# 16V_VBatt_External.net
KiCad netlist of a schematic drawn in Altium Designer
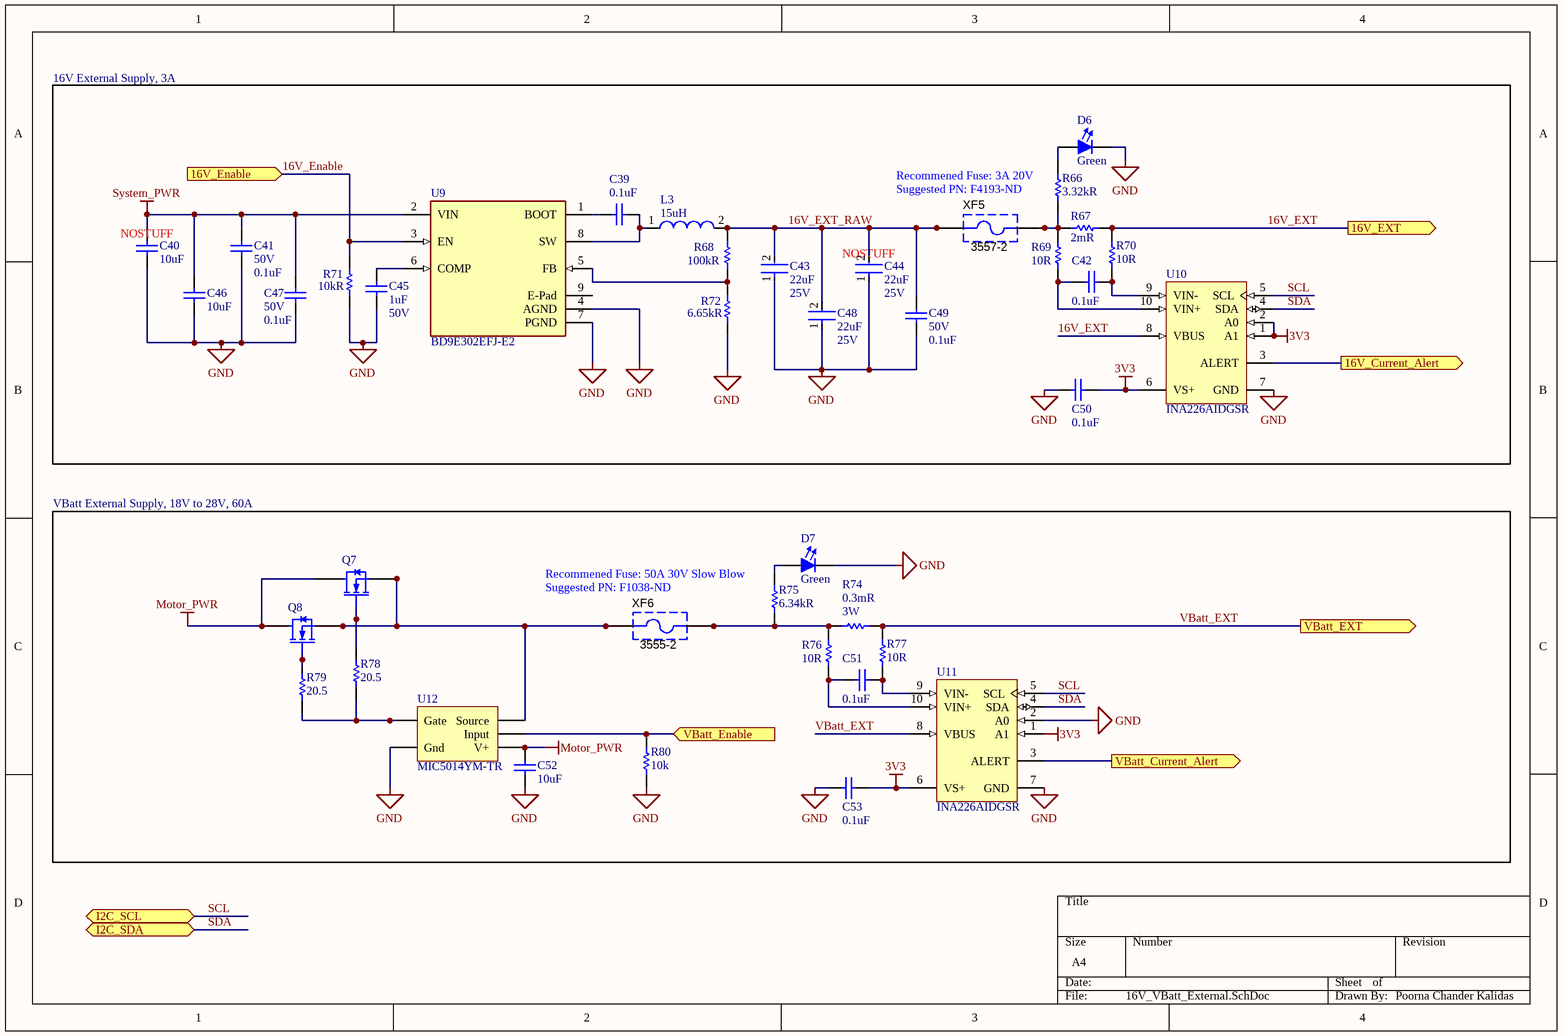
[diagram p0: 16V_VBatt_External.SchDoc]

(export (version "E")
  (design (tool "Eeschema 10.0.6"))
  (components
    (comp (ref "C39")
      (value "CL10B104JB8NNNC")
      (footprint "FP-CL10-0_1-IPC_A")
      (description "CAP CER 0.1UF 50V X7R 0603")
      (fields
        (field (name "TOLERANCE") "5%")
        (field (name "VOLTAGE") "50V")
        (field (name "CAPACITANCE") "0.1uF")
      )
      (libsource (lib "AUVIC") (part "CAP-NP-2"))
    )
    (comp (ref "C40")
      (value "CL31B106KBHNNNE")
      (footprint "CAPC3216X180X50ML20T30")
      (description "Cap Ceramic 10uF 50V X7R 10% Pad SMD 1206 125°C T/R")
      (fields (field (name "CAPACITANCE") "10uF") (field (name "TOLERANCE") "10%"))
      (libsource (lib "AUVIC") (part "CAP-NP-2"))
    )
    (comp (ref "C41")
      (value "CL10B104JB8NNNC")
      (footprint "FP-CL10-0_1-IPC_A")
      (description "CAP CER 0.1UF 50V X7R 0603")
      (fields
        (field (name "TOLERANCE") "5%")
        (field (name "VOLTAGE") "50V")
        (field (name "CAPACITANCE") "0.1uF")
      )
      (libsource (lib "AUVIC") (part "CAP-NP-2"))
    )
    (comp (ref "C42")
      (value "CL10B104JB8NNNC")
      (footprint "FP-CL10-0_1-IPC_A")
      (description "CAP CER 0.1UF 50V X7R 0603")
      (fields
        (field (name "TOLERANCE") "5%")
        (field (name "VOLTAGE") "50V")
        (field (name "CAPACITANCE") "0.1uF")
      )
      (libsource (lib "AUVIC") (part "CAP-NP-2"))
    )
    (comp (ref "C43")
      (value "GRM32ER71E226ME15K")
      (footprint "FP-GRM32-IPC_A")
      (description "CAP CER 22UF 25V X7R 1210")
      (fields
        (field (name "CAPACITANCE") "22uF")
        (field (name "TOLERANCE") "20%")
        (field (name "VOLTAGE") "25V")
      )
      (libsource (lib "AUVIC") (part "b4654b650e69147ec39a6b967a45e02"))
    )
    (comp (ref "C44")
      (value "GRM32ER71E226ME15K")
      (footprint "FP-GRM32-IPC_A")
      (description "CAP CER 22UF 25V X7R 1210")
      (fields
        (field (name "CAPACITANCE") "22uF")
        (field (name "TOLERANCE") "20%")
        (field (name "VOLTAGE") "25V")
      )
      (libsource (lib "AUVIC") (part "b4654b650e69147ec39a6b967a45e02"))
    )
    (comp (ref "C45")
      (value "CL21B105KBFNNNG")
      (footprint "0803 CAP")
      (description "SAMSUNG ELECTRO-MECHANICS - CL21B105KBFNNNG - MLCC CAPACITORS")
      (fields
        (field (name "TOLERANCE") "10%")
        (field (name "CAPACITANCE") "1uF")
        (field (name "VOLTAGE") "50V")
      )
      (libsource (lib "AUVIC") (part "Symbol"))
    )
    (comp (ref "C46")
      (value "CL31B106KBHNNNE")
      (footprint "CAPC3216X180X50ML20T30")
      (description "Cap Ceramic 10uF 50V X7R 10% Pad SMD 1206 125°C T/R")
      (fields (field (name "CAPACITANCE") "10uF") (field (name "TOLERANCE") "10%"))
      (libsource (lib "AUVIC") (part "CAP-NP-2"))
    )
    (comp (ref "C47")
      (value "CL10B104JB8NNNC")
      (footprint "FP-CL10-0_1-IPC_A")
      (description "CAP CER 0.1UF 50V X7R 0603")
      (fields
        (field (name "TOLERANCE") "5%")
        (field (name "VOLTAGE") "50V")
        (field (name "CAPACITANCE") "0.1uF")
      )
      (libsource (lib "AUVIC") (part "CAP-NP-2"))
    )
    (comp (ref "C48")
      (value "GRM32ER71E226ME15K")
      (footprint "FP-GRM32-IPC_A")
      (description "CAP CER 22UF 25V X7R 1210")
      (fields
        (field (name "CAPACITANCE") "22uF")
        (field (name "TOLERANCE") "20%")
        (field (name "VOLTAGE") "25V")
      )
      (libsource (lib "AUVIC") (part "b4654b650e69147ec39a6b967a45e02"))
    )
    (comp (ref "C49")
      (value "CL10B104JB8NNNC")
      (footprint "FP-CL10-0_1-IPC_A")
      (description "CAP CER 0.1UF 50V X7R 0603")
      (fields
        (field (name "TOLERANCE") "5%")
        (field (name "VOLTAGE") "50V")
        (field (name "CAPACITANCE") "0.1uF")
      )
      (libsource (lib "AUVIC") (part "CAP-NP-2"))
    )
    (comp (ref "C50")
      (value "CL10B104JB8NNNC")
      (footprint "FP-CL10-0_1-IPC_A")
      (description "CAP CER 0.1UF 50V X7R 0603")
      (fields
        (field (name "TOLERANCE") "5%")
        (field (name "VOLTAGE") "50V")
        (field (name "CAPACITANCE") "0.1uF")
      )
      (libsource (lib "AUVIC") (part "CAP-NP-2"))
    )
    (comp (ref "C51")
      (value "CL10B104JB8NNNC")
      (footprint "FP-CL10-0_1-IPC_A")
      (description "CAP CER 0.1UF 50V X7R 0603")
      (fields
        (field (name "TOLERANCE") "5%")
        (field (name "VOLTAGE") "50V")
        (field (name "CAPACITANCE") "0.1uF")
      )
      (libsource (lib "AUVIC") (part "CAP-NP-2"))
    )
    (comp (ref "C52")
      (value "CL31B106KBHNNNE")
      (footprint "CAPC3216X180X50ML20T30")
      (description "Cap Ceramic 10uF 50V X7R 10% Pad SMD 1206 125°C T/R")
      (fields (field (name "CAPACITANCE") "10uF") (field (name "TOLERANCE") "10%"))
      (libsource (lib "AUVIC") (part "CAP-NP-2"))
    )
    (comp (ref "C53")
      (value "CL10B104JB8NNNC")
      (footprint "FP-CL10-0_1-IPC_A")
      (description "CAP CER 0.1UF 50V X7R 0603")
      (fields
        (field (name "TOLERANCE") "5%")
        (field (name "VOLTAGE") "50V")
        (field (name "CAPACITANCE") "0.1uF")
      )
      (libsource (lib "AUVIC") (part "CAP-NP-2"))
    )
    (comp (ref "D6")
      (value "LT Q39G-Q1OO-25-1")
      (footprint "FP-LB_Q39E-MFG")
      (description "LED GREEN DIFFUSED 0603 SMD")
      (fields (field (name "COLOR") "Green"))
      (libsource (lib "") (part "Symbol_2"))
    )
    (comp (ref "D7")
      (value "LT Q39G-Q1OO-25-1")
      (footprint "FP-LB_Q39E-MFG")
      (description "LED GREEN DIFFUSED 0603 SMD")
      (fields (field (name "COLOR") "Green"))
      (libsource (lib "") (part "Symbol_2"))
    )
    (comp (ref "L3")
      (value "7447709150")
      (footprint "WE-PD-XXL")
      (fields (field (name "INDUCTANCE") "15uH") (field (name "TOLERANCE") "20%"))
      (libsource (lib "AUVIC") (part "PAS-IND-INDUCTOR-2"))
    )
    (comp (ref "Q7")
      (value "MOSFET N-Channel, 40V, 100A, 272W")
      (footprint "LFPAK-PowerSO8")
      (description "MOSFET N-Channel, 40V, 100A, 272W, Enh-Mode")
      (fields
        (field (name "MFG") "NXP Semiconductors")
        (field (name "PUBLISHER") "AUVic")
        (field (name "CREATED BY") "Ashwin Sira")
        (field (name "REVIEWED_BY") "Ashwin Sira")
      )
      (libsource (lib "AUVIC") (part "MOSFET N-Channel, 40V, 100A, 272W"))
    )
    (comp (ref "Q8")
      (value "MOSFET N-Channel, 40V, 100A, 272W")
      (footprint "LFPAK-PowerSO8")
      (description "MOSFET N-Channel, 40V, 100A, 272W, Enh-Mode")
      (fields
        (field (name "MFG") "NXP Semiconductors")
        (field (name "PUBLISHER") "AUVic")
        (field (name "CREATED BY") "Ashwin Sira")
        (field (name "REVIEWED_BY") "Ashwin Sira")
      )
      (libsource (lib "AUVIC") (part "MOSFET N-Channel, 40V, 100A, 272W"))
    )
    (comp (ref "R66")
      (value "ERJ-3EKF3321V")
      (footprint "RESC1608X55X30ML15T15")
      (description "RES SMD 3.32K OHM 1% 1/10W 0603")
      (fields (field (name "RESISTANCE") "3.32kR") (field (name "TOLERANCE") "1%"))
      (libsource (lib "AUVIC") (part "RES"))
    )
    (comp (ref "R67")
      (value "CSR1206-0R002F1")
      (footprint "RESC2716X08N")
      (description "RES 0.002 OHM 1W 1% 1206")
      (fields (field (name "RESISTANCE") "2mR") (field (name "TOLERANCE") "1%"))
      (libsource (lib "AUVIC") (part "RES"))
    )
    (comp (ref "R68")
      (value "CRCW0603-100KFKEA")
      (footprint "RESC1609X50X30ML10T20")
      (description "Resistor; Thick Film; 100 Kilohms; 0.1 W; 1%; SMT; 0603; TCR 37 ppm/DegC; Tape and Reel")
      (fields (field (name "RESISTANCE") "100kR") (field (name "TOLERANCE") "1%"))
      (libsource (lib "AUVIC") (part "RES"))
    )
    (comp (ref "R69")
      (value "ERJ3EKF10R0V")
      (footprint "FP-ERJ3EK-IPC_A")
      (fields (field (name "RESISTANCE") "10R") (field (name "TOLERANCE") "1%"))
      (libsource (lib "AUVIC") (part "RES"))
    )
    (comp (ref "R70")
      (value "ERJ3EKF10R0V")
      (footprint "FP-ERJ3EK-IPC_A")
      (fields (field (name "RESISTANCE") "10R") (field (name "TOLERANCE") "1%"))
      (libsource (lib "AUVIC") (part "RES"))
    )
    (comp (ref "R71")
      (value "RC0603FR-0710KL")
      (footprint "RESC1608X55X25ML10T15")
      (description "Res General Purpose Thick Film 0603 10K Ohm 1% 1/10W ±100ppm/°C Molded SMD Paper T/R")
      (fields (field (name "RESISTANCE") "10kR") (field (name "TOLERANCE") "1%"))
      (libsource (lib "AUVIC") (part "RES-2"))
    )
    (comp (ref "R72")
      (value "RC0603FR-076K65L")
      (footprint "RESC0603(1608)_M")
      (description "RES SMD 6.65K OHM 1% 1/10W 0603")
      (fields (field (name "TOLERANCE") "1%") (field (name "RESISTANCE") "6.65kR"))
      (libsource (lib "AUVIC") (part "RES"))
    )
    (comp (ref "R74")
      (value "HCS2512FTL300")
      (footprint "RESC6332N(2512\")")
      (fields
        (field (name "RESISTANCE") "0.3mR")
        (field (name "TOLERANCE") "1%")
        (field (name "MAX POWER DISSIPATION") "3W")
      )
      (libsource (lib "") (part "Symbol_1"))
    )
    (comp (ref "R75")
      (value "CRCW06036K34FKEA")
      (footprint "RESC1609X50X30ML10T20")
      (fields (field (name "RESISTANCE") "6.34kR") (field (name "TOLERANCE") "1%"))
      (libsource (lib "AUVIC") (part "RES"))
    )
    (comp (ref "R76")
      (value "ERJ3EKF10R0V")
      (footprint "FP-ERJ3EK-IPC_A")
      (fields (field (name "RESISTANCE") "10R") (field (name "TOLERANCE") "1%"))
      (libsource (lib "AUVIC") (part "RES"))
    )
    (comp (ref "R77")
      (value "ERJ3EKF10R0V")
      (footprint "FP-ERJ3EK-IPC_A")
      (fields (field (name "RESISTANCE") "10R") (field (name "TOLERANCE") "1%"))
      (libsource (lib "AUVIC") (part "RES"))
    )
    (comp (ref "R78")
      (value "20.5")
      (footprint "RESC1608N(0603\")")
      (description "20.5 Ohm, 1%, 1/10W , 0603, SMD")
      (fields (field (name "PUBLISHER") "AUVic") (field (name "CREATED BY") "Gabriel Green"))
      (libsource (lib "") (part "Symbol_1"))
    )
    (comp (ref "R79")
      (value "20.5")
      (footprint "RESC1608N(0603\")")
      (description "20.5 Ohm, 1%, 1/10W , 0603, SMD")
      (fields (field (name "PUBLISHER") "AUVic") (field (name "CREATED BY") "Gabriel Green"))
      (libsource (lib "") (part "Symbol_1"))
    )
    (comp (ref "R80")
      (value "10k")
      (footprint "RESC1608N(0603\")")
      (description "10kR, 1%, 1/10W, 0603 SMD")
      (fields (field (name "MADE BY") "Ashwin Sira"))
      (libsource (lib "") (part "Symbol_1"))
    )
    (comp (ref "U9")
      (value "BD9E302EFJ-E2")
      (footprint "FP-HTSOP-J8-IPC_A")
      (description "IC REG BUCK ADJ 3A 8HTSOP-J")
      (libsource (lib "Altium Content Vault") (part "73ceb71a519c0c64cc3cc0ac2bd1680"))
    )
    (comp (ref "U10")
      (value "INA226AIDGSR")
      (footprint "DGS0010A_M")
      (description "Bi Directional Current and Power Monitor 10-Pin VSSOP T/R")
      (libsource (lib "AUVIC") (part "TI-INA226DGS10"))
    )
    (comp (ref "U11")
      (value "INA226AIDGSR")
      (footprint "DGS0010A_M")
      (description "Bi Directional Current and Power Monitor 10-Pin VSSOP T/R")
      (libsource (lib "AUVIC") (part "TI-INA226DGS10"))
    )
    (comp (ref "U12")
      (value "MIC5014YM-TR")
      (footprint "SOC 8")
      (description "High-Side or Low-Side Gate Driver IC Non-Inverting 8-SOIC")
      (libsource (lib "AUVIC") (part "Gate Driver TTL Logic 3 - 30V"))
    )
    (comp (ref "XF5")
      (value "3557-2")
      (footprint "KSTN-3557-2")
      (description "Fuse Holder; Auto; 2 in1 Blade; THM; 1 Fuse; Vertical; 30 Amps")
      (fields (field (name "VOLTAGE") "500V"))
      (libsource (lib "AUVIC") (part "FUSE_HOLDER-4"))
    )
    (comp (ref "XF6")
      (value "3555-2")
      (footprint "3555-2-Footprint-1")
      (description "FUSE HOLDER MAXI AUTO BLADE PC")
      (fields (field (name "VOLTAGE") "500V"))
      (libsource (lib "AUVIC") (part "FUSE_HOLDER-4"))
    )
  )
  (nets
    (net (code "1") (name "/16V_Current_Alert") (class "Default")
      (node (ref "U10") (pin "3") (pinfunction "ALERT_3") (pintype "open_collector"))
    )
    (net (code "2") (name "/16V_EXT") (class "Default")
      (node (ref "R67") (pin "1") (pinfunction "1_1") (pintype "passive"))
      (node (ref "R70") (pin "1") (pinfunction "1_1") (pintype "passive"))
      (node (ref "U10") (pin "8") (pinfunction "VBUS_8") (pintype "input"))
    )
    (net (code "3") (name "/16V_EXT_RAW") (class "Default")
      (node (ref "C43") (pin "2") (pinfunction "2_2") (pintype "passive"))
      (node (ref "C44") (pin "2") (pinfunction "2_2") (pintype "passive"))
      (node (ref "C48") (pin "2") (pinfunction "2_2") (pintype "passive"))
      (node (ref "C49") (pin "2") (pinfunction "2_2") (pintype "passive"))
      (node (ref "L3") (pin "2") (pinfunction "2_2") (pintype "passive"))
      (node (ref "R68") (pin "2") (pinfunction "2_2") (pintype "passive"))
      (node (ref "XF5") (pin "1") (pinfunction "1_1") (pintype "passive"))
      (node (ref "XF5") (pin "2") (pinfunction "2_2") (pintype "passive"))
    )
    (net (code "4") (name "/16V_Enable") (class "Default")
      (node (ref "R71") (pin "2") (pinfunction "2_2") (pintype "passive"))
      (node (ref "U9") (pin "3") (pinfunction "EN_3") (pintype "input"))
    )
    (net (code "5") (name "/SCL") (class "Default")
      (node (ref "U10") (pin "5") (pinfunction "SCL_5") (pintype "input"))
      (node (ref "U11") (pin "5") (pinfunction "SCL_5") (pintype "input"))
    )
    (net (code "6") (name "/SDA") (class "Default")
      (node (ref "U10") (pin "4") (pinfunction "SDA_4") (pintype "bidirectional"))
      (node (ref "U11") (pin "4") (pinfunction "SDA_4") (pintype "bidirectional"))
    )
    (net (code "7") (name "/VBatt_Current_Alert") (class "Default")
      (node (ref "U11") (pin "3") (pinfunction "ALERT_3") (pintype "open_collector"))
    )
    (net (code "8") (name "/VBatt_EXT") (class "Default")
      (node (ref "R74") (pin "1") (pinfunction "1_1") (pintype "passive"))
      (node (ref "R77") (pin "1") (pinfunction "1_1") (pintype "passive"))
      (node (ref "U11") (pin "8") (pinfunction "VBUS_8") (pintype "input"))
    )
    (net (code "9") (name "/VBatt_Enable") (class "Default")
      (node (ref "R80") (pin "1") (pinfunction "1_1") (pintype "passive"))
      (node (ref "U12") (pin "2") (pinfunction "Input_2") (pintype "passive"))
    )
    (net (code "10") (name "3V3") (class "Default")
      (node (ref "C50") (pin "1") (pinfunction "1_1") (pintype "passive"))
      (node (ref "C53") (pin "1") (pinfunction "1_1") (pintype "passive"))
      (node (ref "U10") (pin "1") (pinfunction "A1_1") (pintype "input"))
      (node (ref "U10") (pin "2") (pinfunction "A0_2") (pintype "input"))
      (node (ref "U10") (pin "6") (pinfunction "VS+_6") (pintype "power_in"))
      (node (ref "U11") (pin "1") (pinfunction "A1_1") (pintype "input"))
      (node (ref "U11") (pin "6") (pinfunction "VS+_6") (pintype "power_in"))
    )
    (net (code "11") (name "GND") (class "Default")
      (node (ref "C40") (pin "2") (pinfunction "2_2") (pintype "passive"))
      (node (ref "C41") (pin "1") (pinfunction "1_1") (pintype "passive"))
      (node (ref "C43") (pin "1") (pinfunction "1_1") (pintype "passive"))
      (node (ref "C44") (pin "1") (pinfunction "1_1") (pintype "passive"))
      (node (ref "C45") (pin "1") (pinfunction "1_1") (pintype "passive"))
      (node (ref "C46") (pin "2") (pinfunction "2_2") (pintype "passive"))
      (node (ref "C47") (pin "1") (pinfunction "1_1") (pintype "passive"))
      (node (ref "C48") (pin "1") (pinfunction "1_1") (pintype "passive"))
      (node (ref "C49") (pin "1") (pinfunction "1_1") (pintype "passive"))
      (node (ref "C50") (pin "2") (pinfunction "2_2") (pintype "passive"))
      (node (ref "C52") (pin "2") (pinfunction "2_2") (pintype "passive"))
      (node (ref "C53") (pin "2") (pinfunction "2_2") (pintype "passive"))
      (node (ref "D6") (pin "1") (pinfunction "Cathode_1") (pintype "passive"))
      (node (ref "D7") (pin "1") (pinfunction "Cathode_1") (pintype "passive"))
      (node (ref "R71") (pin "1") (pinfunction "1_1") (pintype "passive"))
      (node (ref "R72") (pin "1") (pinfunction "1_1") (pintype "passive"))
      (node (ref "R80") (pin "2") (pinfunction "2_2") (pintype "passive"))
      (node (ref "U10") (pin "7") (pinfunction "GND_7") (pintype "power_in"))
      (node (ref "U11") (pin "2") (pinfunction "A0_2") (pintype "input"))
      (node (ref "U11") (pin "7") (pinfunction "GND_7") (pintype "power_in"))
      (node (ref "U12") (pin "4") (pinfunction "Gnd_4") (pintype "passive"))
      (node (ref "U9") (pin "4") (pinfunction "AGND_4") (pintype "power_in"))
      (node (ref "U9") (pin "7") (pinfunction "PGND_7") (pintype "power_in"))
    )
    (net (code "12") (name "Motor_PWR") (class "Default")
      (node (ref "C52") (pin "1") (pinfunction "1_1") (pintype "passive"))
      (node (ref "Q7") (pin "5") (pinfunction "Drain_5") (pintype "power_in"))
      (node (ref "Q8") (pin "5") (pinfunction "Drain_5") (pintype "power_in"))
      (node (ref "U12") (pin "1") (pinfunction "V+_1") (pintype "passive"))
    )
    (net (code "13") (name "Net-(D6-Anode)") (class "Default")
      (node (ref "D6") (pin "2") (pinfunction "Anode_2") (pintype "passive"))
      (node (ref "R66") (pin "1") (pinfunction "1_1") (pintype "passive"))
    )
    (net (code "14") (name "Net-(D7-Anode)") (class "Default")
      (node (ref "D7") (pin "2") (pinfunction "Anode_2") (pintype "passive"))
      (node (ref "R75") (pin "2") (pinfunction "2_2") (pintype "passive"))
    )
    (net (code "15") (name "Net-(Q7-Gate)") (class "Default")
      (node (ref "Q7") (pin "4") (pinfunction "Gate_4") (pintype "power_in"))
      (node (ref "R78") (pin "1") (pinfunction "1_1") (pintype "passive"))
    )
    (net (code "16") (name "Net-(Q8-Gate)") (class "Default")
      (node (ref "Q8") (pin "4") (pinfunction "Gate_4") (pintype "power_in"))
      (node (ref "R79") (pin "1") (pinfunction "1_1") (pintype "passive"))
    )
    (net (code "17") (name "Net-(R66-Pad2)") (class "Default")
      (node (ref "R66") (pin "2") (pinfunction "2_2") (pintype "passive"))
      (node (ref "R67") (pin "2") (pinfunction "2_2") (pintype "passive"))
      (node (ref "R69") (pin "1") (pinfunction "1_1") (pintype "passive"))
      (node (ref "XF5") (pin "3") (pinfunction "3_3") (pintype "passive"))
      (node (ref "XF5") (pin "4") (pinfunction "4_4") (pintype "passive"))
    )
    (net (code "18") (name "Net-(R74-Pad2)") (class "Default")
      (node (ref "R74") (pin "2") (pinfunction "2_2") (pintype "passive"))
      (node (ref "R75") (pin "1") (pinfunction "1_1") (pintype "passive"))
      (node (ref "R76") (pin "1") (pinfunction "1_1") (pintype "passive"))
      (node (ref "XF6") (pin "3") (pinfunction "3_3") (pintype "passive"))
      (node (ref "XF6") (pin "4") (pinfunction "4_4") (pintype "passive"))
    )
    (net (code "19") (name "Net-(U9-BOOT)") (class "Default")
      (node (ref "C39") (pin "1") (pinfunction "1_1") (pintype "passive"))
      (node (ref "U9") (pin "1") (pinfunction "BOOT_1") (pintype "passive"))
    )
    (net (code "20") (name "Net-(U9-COMP)") (class "Default")
      (node (ref "C45") (pin "2") (pinfunction "2_2") (pintype "passive"))
      (node (ref "U9") (pin "6") (pinfunction "COMP_6") (pintype "input"))
    )
    (net (code "21") (name "Net-(U9-FB)") (class "Default")
      (node (ref "R68") (pin "1") (pinfunction "1_1") (pintype "passive"))
      (node (ref "R72") (pin "2") (pinfunction "2_2") (pintype "passive"))
      (node (ref "U9") (pin "5") (pinfunction "FB_5") (pintype "input"))
    )
    (net (code "22") (name "Net-(U9-SW)") (class "Default")
      (node (ref "C39") (pin "2") (pinfunction "2_2") (pintype "passive"))
      (node (ref "L3") (pin "1") (pinfunction "1_1") (pintype "passive"))
      (node (ref "U9") (pin "8") (pinfunction "SW_8") (pintype "passive"))
    )
    (net (code "23") (name "Net-(U10-VIN+)") (class "Default")
      (node (ref "C42") (pin "2") (pinfunction "2_2") (pintype "passive"))
      (node (ref "R69") (pin "2") (pinfunction "2_2") (pintype "passive"))
      (node (ref "U10") (pin "10") (pinfunction "VIN+_10") (pintype "input"))
    )
    (net (code "24") (name "Net-(U10-VIN-)") (class "Default")
      (node (ref "C42") (pin "1") (pinfunction "1_1") (pintype "passive"))
      (node (ref "R70") (pin "2") (pinfunction "2_2") (pintype "passive"))
      (node (ref "U10") (pin "9") (pinfunction "VIN-_9") (pintype "input"))
    )
    (net (code "25") (name "Net-(U11-VIN+)") (class "Default")
      (node (ref "C51") (pin "2") (pinfunction "2_2") (pintype "passive"))
      (node (ref "R76") (pin "2") (pinfunction "2_2") (pintype "passive"))
      (node (ref "U11") (pin "10") (pinfunction "VIN+_10") (pintype "input"))
    )
    (net (code "26") (name "Net-(U11-VIN-)") (class "Default")
      (node (ref "C51") (pin "1") (pinfunction "1_1") (pintype "passive"))
      (node (ref "R77") (pin "2") (pinfunction "2_2") (pintype "passive"))
      (node (ref "U11") (pin "9") (pinfunction "VIN-_9") (pintype "input"))
    )
    (net (code "27") (name "Net-(U12-Gate)") (class "Default")
      (node (ref "R78") (pin "2") (pinfunction "2_2") (pintype "passive"))
      (node (ref "R79") (pin "2") (pinfunction "2_2") (pintype "passive"))
      (node (ref "U12") (pin "5") (pinfunction "Gate_5") (pintype "passive"))
    )
    (net (code "28") (name "Net-(U12-Source)") (class "Default")
      (node (ref "Q7") (pin "1") (pinfunction "Source_1") (pintype "power_in"))
      (node (ref "Q7") (pin "2") (pinfunction "Source_2") (pintype "power_in"))
      (node (ref "Q7") (pin "3") (pinfunction "Source_3") (pintype "power_in"))
      (node (ref "Q8") (pin "1") (pinfunction "Source_1") (pintype "power_in"))
      (node (ref "Q8") (pin "2") (pinfunction "Source_2") (pintype "power_in"))
      (node (ref "Q8") (pin "3") (pinfunction "Source_3") (pintype "power_in"))
      (node (ref "U12") (pin "3") (pinfunction "Source_3") (pintype "passive"))
      (node (ref "XF6") (pin "1") (pinfunction "1_1") (pintype "passive"))
      (node (ref "XF6") (pin "2") (pinfunction "2_2") (pintype "passive"))
    )
    (net (code "29") (name "System_PWR") (class "Default")
      (node (ref "C40") (pin "1") (pinfunction "1_1") (pintype "passive"))
      (node (ref "C41") (pin "2") (pinfunction "2_2") (pintype "passive"))
      (node (ref "C46") (pin "1") (pinfunction "1_1") (pintype "passive"))
      (node (ref "C47") (pin "2") (pinfunction "2_2") (pintype "passive"))
      (node (ref "U9") (pin "2") (pinfunction "VIN_2") (pintype "power_in"))
    )
    (net (code "30") (name "unconnected-(U9-E-Pad-Pad9)") (class "Default")
      (node (ref "U9") (pin "9") (pinfunction "E-Pad_9") (pintype "power_in"))
    )
  )
)
